# ActiveMarkerDeck.net
KiCad netlist of a schematic drawn in Altium Designer
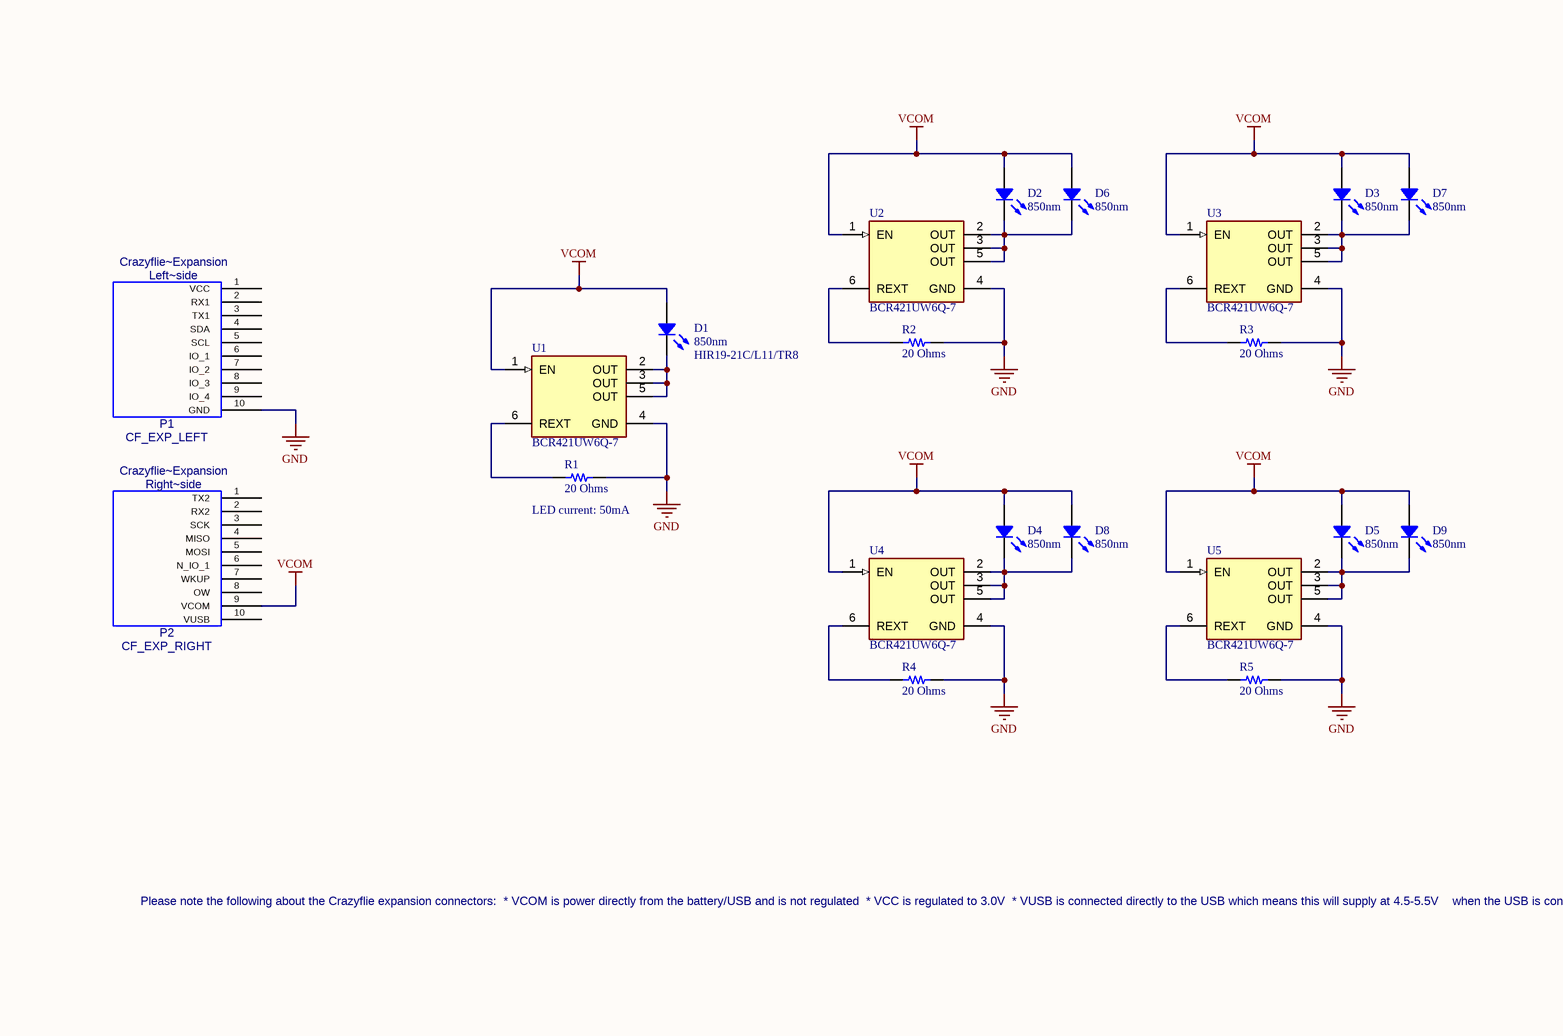
[diagram p0: ActiveMarkerDeck.SchDoc]

(export (version "E")
  (design (tool "Eeschema 10.0.6"))
  (components
    (comp (ref "D1")
      (value "850nm")
      (footprint "LED 0603_1608 RED")
      (description "LED RED SMD")
      (fields
        (field (name "PART NUMBER") "CL-196HR-CD-T")
        (field (name "MANUFACTURER") "Citizen")
        (field (name "SUPPLIER PART NUMBER 1") "HIR19-21C/L11/TR8")
      )
      (libsource (lib "Celestial Altium Library - altium_library") (part "LED"))
    )
    (comp (ref "D2")
      (value "850nm")
      (footprint "LED 0603_1608 RED")
      (description "LED RED SMD")
      (fields (field (name "PART NUMBER") "CL-196HR-CD-T") (field (name "MANUFACTURER") "Citizen"))
      (libsource (lib "Celestial Altium Library - altium_library") (part "LED"))
    )
    (comp (ref "D3")
      (value "850nm")
      (footprint "LED 0603_1608 RED")
      (description "LED RED SMD")
      (fields (field (name "PART NUMBER") "CL-196HR-CD-T") (field (name "MANUFACTURER") "Citizen"))
      (libsource (lib "Celestial Altium Library - altium_library") (part "LED"))
    )
    (comp (ref "D4")
      (value "850nm")
      (footprint "LED 0603_1608 RED")
      (description "LED RED SMD")
      (fields (field (name "PART NUMBER") "CL-196HR-CD-T") (field (name "MANUFACTURER") "Citizen"))
      (libsource (lib "Celestial Altium Library - altium_library") (part "LED"))
    )
    (comp (ref "D5")
      (value "850nm")
      (footprint "LED 0603_1608 RED")
      (description "LED RED SMD")
      (fields (field (name "PART NUMBER") "CL-196HR-CD-T") (field (name "MANUFACTURER") "Citizen"))
      (libsource (lib "Celestial Altium Library - altium_library") (part "LED"))
    )
    (comp (ref "D6")
      (value "850nm")
      (footprint "LED 0603_1608 RED")
      (description "LED RED SMD")
      (fields (field (name "PART NUMBER") "CL-196HR-CD-T") (field (name "MANUFACTURER") "Citizen"))
      (libsource (lib "Celestial Altium Library - altium_library") (part "LED"))
    )
    (comp (ref "D7")
      (value "850nm")
      (footprint "LED 0603_1608 RED")
      (description "LED RED SMD")
      (fields (field (name "PART NUMBER") "CL-196HR-CD-T") (field (name "MANUFACTURER") "Citizen"))
      (libsource (lib "Celestial Altium Library - altium_library") (part "LED"))
    )
    (comp (ref "D8")
      (value "850nm")
      (footprint "LED 0603_1608 RED")
      (description "LED RED SMD")
      (fields (field (name "PART NUMBER") "CL-196HR-CD-T") (field (name "MANUFACTURER") "Citizen"))
      (libsource (lib "Celestial Altium Library - altium_library") (part "LED"))
    )
    (comp (ref "D9")
      (value "850nm")
      (footprint "LED 0603_1608 RED")
      (description "LED RED SMD")
      (fields (field (name "PART NUMBER") "CL-196HR-CD-T") (field (name "MANUFACTURER") "Citizen"))
      (libsource (lib "Celestial Altium Library - altium_library") (part "LED"))
    )
    (comp (ref "P1") (value "CF_EXP_LEFT") (libsource (lib "*") (part "CF_EXP_LEFT")))
    (comp (ref "P2") (value "CF_EXP_RIGHT") (libsource (lib "*") (part "CF_EXP_RIGHT")))
    (comp (ref "R1")
      (value "20 Ohms")
      (footprint "RES 0603_1608")
      (description "RES 20 OHM 5% 1/10W 0603")
      (fields (field (name "PART NUMBER") "RC0603JR-0720RL") (field (name "MANUFACTURER") "Yageo"))
      (libsource (lib "Celestial Altium Library - altium_library") (part "Resistor"))
    )
    (comp (ref "R2")
      (value "20 Ohms")
      (footprint "RES 0603_1608")
      (description "RES 20 OHM 5% 1/10W 0603")
      (fields (field (name "PART NUMBER") "RC0603JR-0720RL") (field (name "MANUFACTURER") "Yageo"))
      (libsource (lib "Celestial Altium Library - altium_library") (part "Resistor"))
    )
    (comp (ref "R3")
      (value "20 Ohms")
      (footprint "RES 0603_1608")
      (description "RES 20 OHM 5% 1/10W 0603")
      (fields (field (name "PART NUMBER") "RC0603JR-0720RL") (field (name "MANUFACTURER") "Yageo"))
      (libsource (lib "Celestial Altium Library - altium_library") (part "Resistor"))
    )
    (comp (ref "R4")
      (value "20 Ohms")
      (footprint "RES 0603_1608")
      (description "RES 20 OHM 5% 1/10W 0603")
      (fields (field (name "PART NUMBER") "RC0603JR-0720RL") (field (name "MANUFACTURER") "Yageo"))
      (libsource (lib "Celestial Altium Library - altium_library") (part "Resistor"))
    )
    (comp (ref "R5")
      (value "20 Ohms")
      (footprint "RES 0603_1608")
      (description "RES 20 OHM 5% 1/10W 0603")
      (fields (field (name "PART NUMBER") "RC0603JR-0720RL") (field (name "MANUFACTURER") "Yageo"))
      (libsource (lib "Celestial Altium Library - altium_library") (part "Resistor"))
    )
    (comp (ref "U1")
      (value "BCR421UW6Q-7")
      (footprint "FP-SOT26_SC74R-MFG")
      (description "TRANSISTOR LED DRIVER SOT26 T&R")
      (fields
        (field (name "MANUFACTURER") "Diodes Inc.")
        (field (name "OCTOPART") "https://octopart.com/bcr421uw6q-7-diodes+inc.-67219224")
      )
      (libsource (lib "Altium Content Vault") (part "ad914be0572bb629e6d009380f5a8f4"))
    )
    (comp (ref "U2")
      (value "BCR421UW6Q-7")
      (footprint "FP-SOT26_SC74R-MFG")
      (description "TRANSISTOR LED DRIVER SOT26 T&R")
      (fields
        (field (name "MANUFACTURER") "Diodes Inc.")
        (field (name "OCTOPART") "https://octopart.com/bcr421uw6q-7-diodes+inc.-67219224")
      )
      (libsource (lib "Altium Content Vault") (part "ad914be0572bb629e6d009380f5a8f4"))
    )
    (comp (ref "U3")
      (value "BCR421UW6Q-7")
      (footprint "FP-SOT26_SC74R-MFG")
      (description "TRANSISTOR LED DRIVER SOT26 T&R")
      (fields
        (field (name "MANUFACTURER") "Diodes Inc.")
        (field (name "OCTOPART") "https://octopart.com/bcr421uw6q-7-diodes+inc.-67219224")
      )
      (libsource (lib "Altium Content Vault") (part "ad914be0572bb629e6d009380f5a8f4"))
    )
    (comp (ref "U4")
      (value "BCR421UW6Q-7")
      (footprint "FP-SOT26_SC74R-MFG")
      (description "TRANSISTOR LED DRIVER SOT26 T&R")
      (fields
        (field (name "MANUFACTURER") "Diodes Inc.")
        (field (name "OCTOPART") "https://octopart.com/bcr421uw6q-7-diodes+inc.-67219224")
      )
      (libsource (lib "Altium Content Vault") (part "ad914be0572bb629e6d009380f5a8f4"))
    )
    (comp (ref "U5")
      (value "BCR421UW6Q-7")
      (footprint "FP-SOT26_SC74R-MFG")
      (description "TRANSISTOR LED DRIVER SOT26 T&R")
      (fields
        (field (name "MANUFACTURER") "Diodes Inc.")
        (field (name "OCTOPART") "https://octopart.com/bcr421uw6q-7-diodes+inc.-67219224")
      )
      (libsource (lib "Altium Content Vault") (part "ad914be0572bb629e6d009380f5a8f4"))
    )
  )
  (nets
    (net (code "1") (name "GND") (class "Default")
      (node (ref "P1") (pin "10") (pinfunction "GND_10") (pintype "passive"))
      (node (ref "R1") (pin "2") (pinfunction "2_2") (pintype "passive"))
      (node (ref "R2") (pin "2") (pinfunction "2_2") (pintype "passive"))
      (node (ref "R3") (pin "2") (pinfunction "2_2") (pintype "passive"))
      (node (ref "R4") (pin "2") (pinfunction "2_2") (pintype "passive"))
      (node (ref "R5") (pin "2") (pinfunction "2_2") (pintype "passive"))
      (node (ref "U1") (pin "4") (pinfunction "GND_4") (pintype "power_in"))
      (node (ref "U2") (pin "4") (pinfunction "GND_4") (pintype "power_in"))
      (node (ref "U3") (pin "4") (pinfunction "GND_4") (pintype "power_in"))
      (node (ref "U4") (pin "4") (pinfunction "GND_4") (pintype "power_in"))
      (node (ref "U5") (pin "4") (pinfunction "GND_4") (pintype "power_in"))
    )
    (net (code "2") (name "Net-(D1-Pad2)") (class "Default")
      (node (ref "D1") (pin "2") (pinfunction "2_2") (pintype "passive"))
      (node (ref "U1") (pin "2") (pinfunction "OUT_2") (pintype "passive"))
      (node (ref "U1") (pin "3") (pinfunction "OUT_3") (pintype "passive"))
      (node (ref "U1") (pin "5") (pinfunction "OUT_5") (pintype "passive"))
    )
    (net (code "3") (name "Net-(D2-Pad2)") (class "Default")
      (node (ref "D2") (pin "2") (pinfunction "2_2") (pintype "passive"))
      (node (ref "D6") (pin "2") (pinfunction "2_2") (pintype "passive"))
      (node (ref "U2") (pin "2") (pinfunction "OUT_2") (pintype "passive"))
      (node (ref "U2") (pin "3") (pinfunction "OUT_3") (pintype "passive"))
      (node (ref "U2") (pin "5") (pinfunction "OUT_5") (pintype "passive"))
    )
    (net (code "4") (name "Net-(D3-Pad2)") (class "Default")
      (node (ref "D3") (pin "2") (pinfunction "2_2") (pintype "passive"))
      (node (ref "D7") (pin "2") (pinfunction "2_2") (pintype "passive"))
      (node (ref "U3") (pin "2") (pinfunction "OUT_2") (pintype "passive"))
      (node (ref "U3") (pin "3") (pinfunction "OUT_3") (pintype "passive"))
      (node (ref "U3") (pin "5") (pinfunction "OUT_5") (pintype "passive"))
    )
    (net (code "5") (name "Net-(D4-Pad2)") (class "Default")
      (node (ref "D4") (pin "2") (pinfunction "2_2") (pintype "passive"))
      (node (ref "D8") (pin "2") (pinfunction "2_2") (pintype "passive"))
      (node (ref "U4") (pin "2") (pinfunction "OUT_2") (pintype "passive"))
      (node (ref "U4") (pin "3") (pinfunction "OUT_3") (pintype "passive"))
      (node (ref "U4") (pin "5") (pinfunction "OUT_5") (pintype "passive"))
    )
    (net (code "6") (name "Net-(D5-Pad2)") (class "Default")
      (node (ref "D5") (pin "2") (pinfunction "2_2") (pintype "passive"))
      (node (ref "D9") (pin "2") (pinfunction "2_2") (pintype "passive"))
      (node (ref "U5") (pin "2") (pinfunction "OUT_2") (pintype "passive"))
      (node (ref "U5") (pin "3") (pinfunction "OUT_3") (pintype "passive"))
      (node (ref "U5") (pin "5") (pinfunction "OUT_5") (pintype "passive"))
    )
    (net (code "7") (name "Net-(U1-REXT)") (class "Default")
      (node (ref "R1") (pin "1") (pinfunction "1_1") (pintype "passive"))
      (node (ref "U1") (pin "6") (pinfunction "REXT_6") (pintype "passive"))
    )
    (net (code "8") (name "Net-(U2-REXT)") (class "Default")
      (node (ref "R2") (pin "1") (pinfunction "1_1") (pintype "passive"))
      (node (ref "U2") (pin "6") (pinfunction "REXT_6") (pintype "passive"))
    )
    (net (code "9") (name "Net-(U3-REXT)") (class "Default")
      (node (ref "R3") (pin "1") (pinfunction "1_1") (pintype "passive"))
      (node (ref "U3") (pin "6") (pinfunction "REXT_6") (pintype "passive"))
    )
    (net (code "10") (name "Net-(U4-REXT)") (class "Default")
      (node (ref "R4") (pin "1") (pinfunction "1_1") (pintype "passive"))
      (node (ref "U4") (pin "6") (pinfunction "REXT_6") (pintype "passive"))
    )
    (net (code "11") (name "Net-(U5-REXT)") (class "Default")
      (node (ref "R5") (pin "1") (pinfunction "1_1") (pintype "passive"))
      (node (ref "U5") (pin "6") (pinfunction "REXT_6") (pintype "passive"))
    )
    (net (code "12") (name "VCOM") (class "Default")
      (node (ref "D1") (pin "1") (pinfunction "1_1") (pintype "passive"))
      (node (ref "D2") (pin "1") (pinfunction "1_1") (pintype "passive"))
      (node (ref "D3") (pin "1") (pinfunction "1_1") (pintype "passive"))
      (node (ref "D4") (pin "1") (pinfunction "1_1") (pintype "passive"))
      (node (ref "D5") (pin "1") (pinfunction "1_1") (pintype "passive"))
      (node (ref "D6") (pin "1") (pinfunction "1_1") (pintype "passive"))
      (node (ref "D7") (pin "1") (pinfunction "1_1") (pintype "passive"))
      (node (ref "D8") (pin "1") (pinfunction "1_1") (pintype "passive"))
      (node (ref "D9") (pin "1") (pinfunction "1_1") (pintype "passive"))
      (node (ref "P2") (pin "9") (pinfunction "VCOM_9") (pintype "passive"))
      (node (ref "U1") (pin "1") (pinfunction "EN_1") (pintype "input"))
      (node (ref "U2") (pin "1") (pinfunction "EN_1") (pintype "input"))
      (node (ref "U3") (pin "1") (pinfunction "EN_1") (pintype "input"))
      (node (ref "U4") (pin "1") (pinfunction "EN_1") (pintype "input"))
      (node (ref "U5") (pin "1") (pinfunction "EN_1") (pintype "input"))
    )
    (net (code "13") (name "unconnected-(P1-IO_1-Pad6)") (class "Default")
      (node (ref "P1") (pin "6") (pinfunction "IO_1_6") (pintype "passive"))
    )
    (net (code "14") (name "unconnected-(P1-IO_2-Pad7)") (class "Default")
      (node (ref "P1") (pin "7") (pinfunction "IO_2_7") (pintype "passive"))
    )
    (net (code "15") (name "unconnected-(P1-IO_3-Pad8)") (class "Default")
      (node (ref "P1") (pin "8") (pinfunction "IO_3_8") (pintype "passive"))
    )
    (net (code "16") (name "unconnected-(P1-IO_4-Pad9)") (class "Default")
      (node (ref "P1") (pin "9") (pinfunction "IO_4_9") (pintype "passive"))
    )
    (net (code "17") (name "unconnected-(P1-RX1-Pad2)") (class "Default")
      (node (ref "P1") (pin "2") (pinfunction "RX1_2") (pintype "passive"))
    )
    (net (code "18") (name "unconnected-(P1-SCL-Pad5)") (class "Default")
      (node (ref "P1") (pin "5") (pinfunction "SCL_5") (pintype "passive"))
    )
    (net (code "19") (name "unconnected-(P1-SDA-Pad4)") (class "Default")
      (node (ref "P1") (pin "4") (pinfunction "SDA_4") (pintype "passive"))
    )
    (net (code "20") (name "unconnected-(P1-TX1-Pad3)") (class "Default")
      (node (ref "P1") (pin "3") (pinfunction "TX1_3") (pintype "passive"))
    )
    (net (code "21") (name "unconnected-(P1-VCC-Pad1)") (class "Default")
      (node (ref "P1") (pin "1") (pinfunction "VCC_1") (pintype "passive"))
    )
    (net (code "22") (name "unconnected-(P2-MISO-Pad4)") (class "Default")
      (node (ref "P2") (pin "4") (pinfunction "MISO_4") (pintype "passive"))
    )
    (net (code "23") (name "unconnected-(P2-MOSI-Pad5)") (class "Default")
      (node (ref "P2") (pin "5") (pinfunction "MOSI_5") (pintype "passive"))
    )
    (net (code "24") (name "unconnected-(P2-N_IO_1-Pad6)") (class "Default")
      (node (ref "P2") (pin "6") (pinfunction "N_IO_1_6") (pintype "passive"))
    )
    (net (code "25") (name "unconnected-(P2-OW-Pad8)") (class "Default")
      (node (ref "P2") (pin "8") (pinfunction "OW_8") (pintype "passive"))
    )
    (net (code "26") (name "unconnected-(P2-RX2-Pad2)") (class "Default")
      (node (ref "P2") (pin "2") (pinfunction "RX2_2") (pintype "passive"))
    )
    (net (code "27") (name "unconnected-(P2-SCK-Pad3)") (class "Default")
      (node (ref "P2") (pin "3") (pinfunction "SCK_3") (pintype "passive"))
    )
    (net (code "28") (name "unconnected-(P2-TX2-Pad1)") (class "Default")
      (node (ref "P2") (pin "1") (pinfunction "TX2_1") (pintype "passive"))
    )
    (net (code "29") (name "unconnected-(P2-VUSB-Pad10)") (class "Default")
      (node (ref "P2") (pin "10") (pinfunction "VUSB_10") (pintype "passive"))
    )
    (net (code "30") (name "unconnected-(P2-WKUP-Pad7)") (class "Default")
      (node (ref "P2") (pin "7") (pinfunction "WKUP_7") (pintype "passive"))
    )
  )
)
